# ADXL345_Breakout_V15panelize.net
KiCad netlist of a schematic drawn in EAGLE
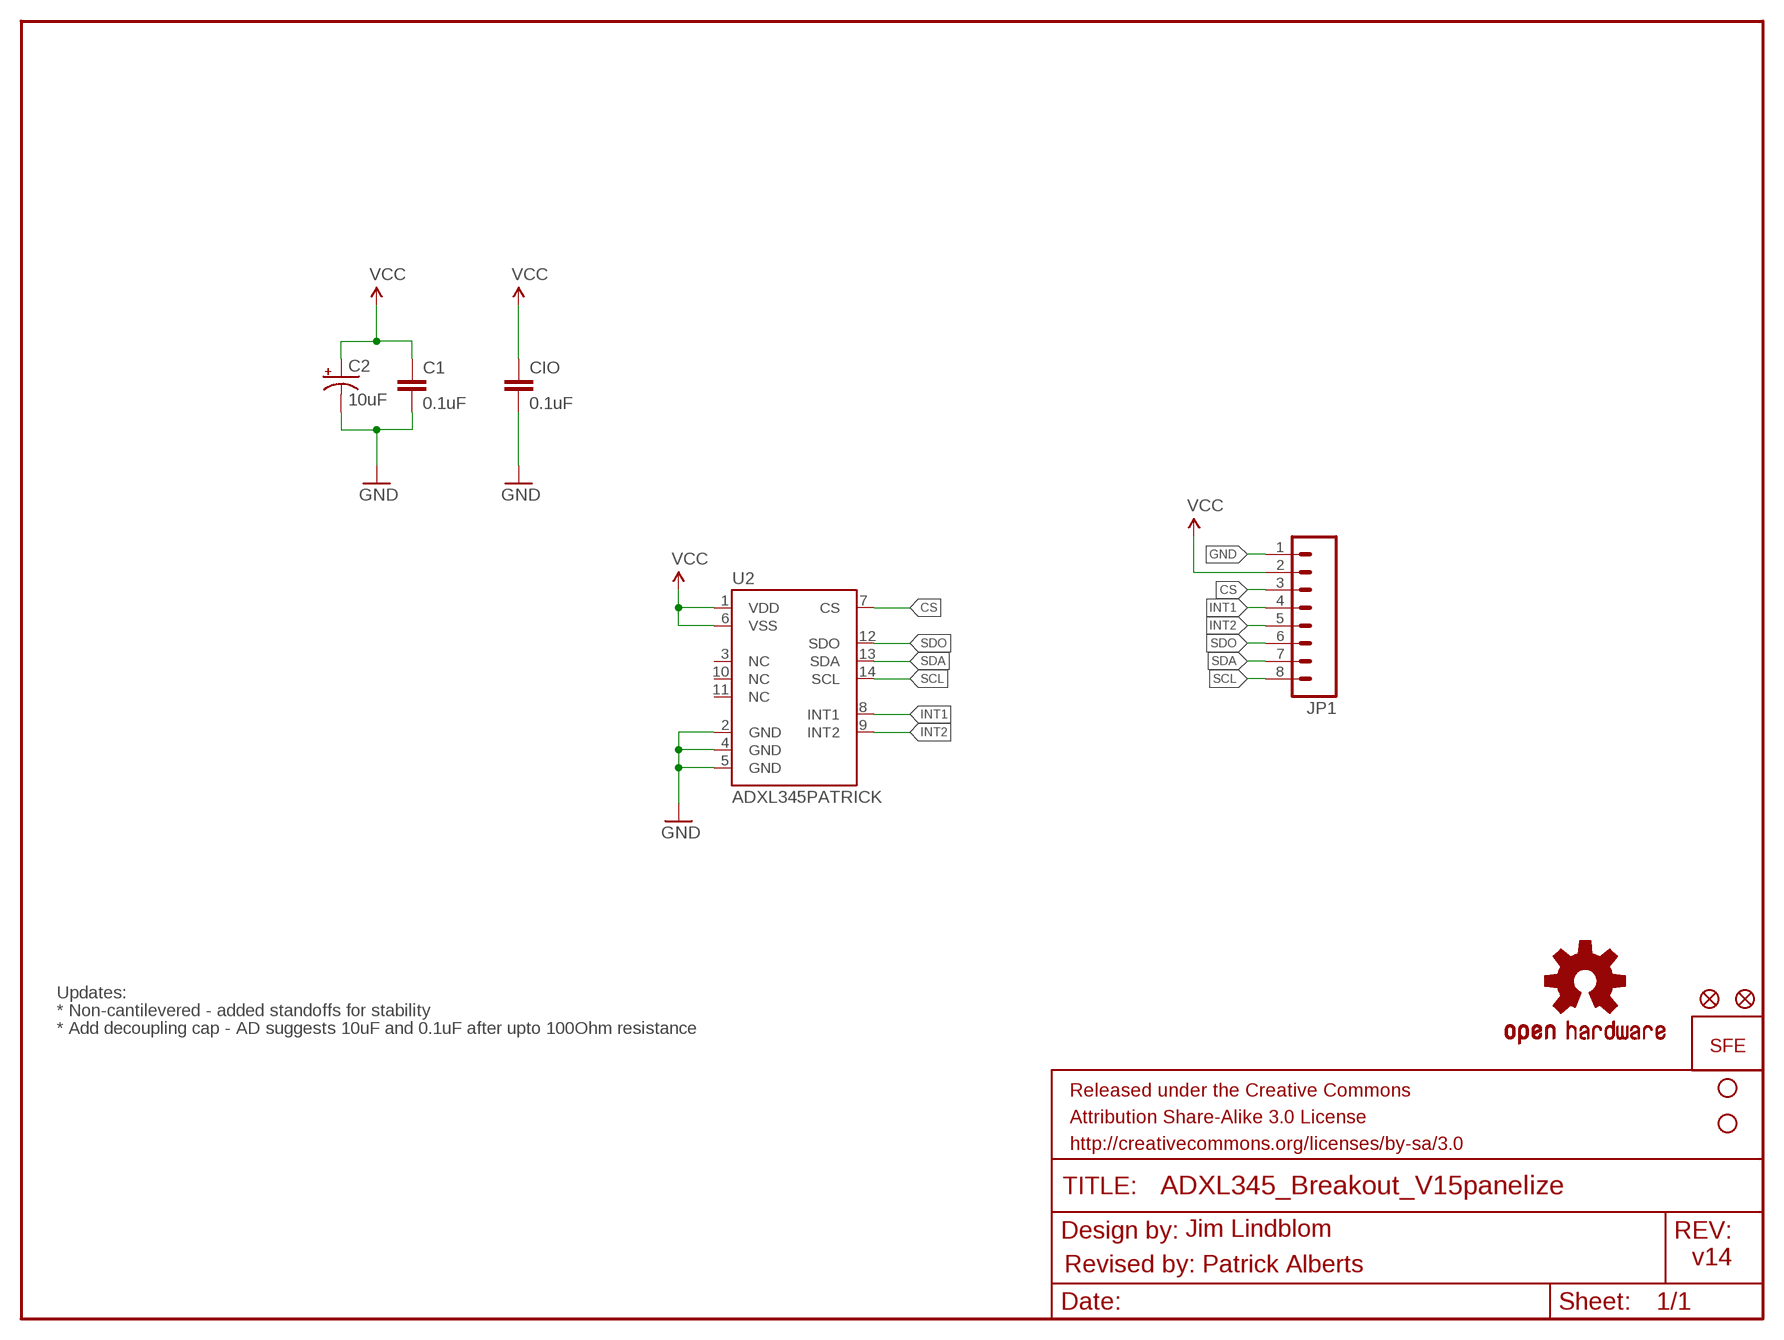
[diagram p0: schematic, sheet 1]

(export (version "E")
  (design (tool "Eeschema 10.0.6"))
  (components
    (comp (ref "C1")
      (value "0.1uF")
      (footprint "eagle-import:0805")
      (libsource (lib "eagle-import") (part "CAP0805"))
    )
    (comp (ref "C2")
      (value "10uF")
      (footprint "eagle-import:EIA3216")
      (libsource (lib "eagle-import") (part "CAP_POL1206"))
    )
    (comp (ref "CIO")
      (value "0.1uF")
      (footprint "eagle-import:0805")
      (libsource (lib "eagle-import") (part "CAP0805"))
    )
    (comp (ref "JP1")
      (value "M081X08")
      (footprint "eagle-import:1X08")
      (libsource (lib "eagle-import") (part "M081X08"))
    )
    (comp (ref "JP2")
      (value "STAND-OFF")
      (footprint "eagle-import:STAND-OFF")
      (libsource (lib "eagle-import") (part "STAND-OFF"))
    )
    (comp (ref "JP3")
      (value "STAND-OFF")
      (footprint "eagle-import:STAND-OFF")
      (libsource (lib "eagle-import") (part "STAND-OFF"))
    )
    (comp (ref "JP4")
      (value "FIDUCIAL1X2")
      (footprint "eagle-import:FIDUCIAL-1X2")
      (libsource (lib "eagle-import") (part "FIDUCIAL1X2"))
    )
    (comp (ref "JP5")
      (value "FIDUCIAL1X2")
      (footprint "eagle-import:FIDUCIAL-1X2")
      (libsource (lib "eagle-import") (part "FIDUCIAL1X2"))
    )
    (comp (ref "U$2")
      (value "LOGO-SFENEW")
      (footprint "eagle-import:SFE-NEW-WEBLOGO")
      (libsource (lib "eagle-import") (part "LOGO-SFENEW"))
    )
    (comp (ref "U$3")
      (value "OSHW-LOGOS")
      (footprint "eagle-import:OSHW-LOGO-S")
      (libsource (lib "eagle-import") (part "OSHW-LOGOS"))
    )
    (comp (ref "U2")
      (value "ADXL345PATRICK")
      (footprint "eagle-import:LGA14_1_1_PATRICK")
      (libsource (lib "eagle-import") (part "ADXL345PATRICK"))
    )
  )
  (nets
    (net (code "1") (name "CS") (class "Default")
      (node (ref "JP1") (pin "3") (pinfunction "3_3") (pintype "passive"))
      (node (ref "U2") (pin "7") (pinfunction "CS_7") (pintype "bidirectional"))
    )
    (net (code "2") (name "GND") (class "Default")
      (node (ref "C1") (pin "2") (pinfunction "2_2") (pintype "passive"))
      (node (ref "C2") (pin "C") (pinfunction "-_C") (pintype "passive"))
      (node (ref "CIO") (pin "2") (pinfunction "2_2") (pintype "passive"))
      (node (ref "JP1") (pin "1") (pinfunction "1_1") (pintype "passive"))
      (node (ref "U2") (pin "2") (pinfunction "GND_2") (pintype "bidirectional"))
      (node (ref "U2") (pin "4") (pinfunction "GND_4") (pintype "bidirectional"))
      (node (ref "U2") (pin "5") (pinfunction "GND_5") (pintype "bidirectional"))
    )
    (net (code "3") (name "INT1") (class "Default")
      (node (ref "JP1") (pin "4") (pinfunction "4_4") (pintype "passive"))
      (node (ref "U2") (pin "8") (pinfunction "INT1_8") (pintype "bidirectional"))
    )
    (net (code "4") (name "INT2") (class "Default")
      (node (ref "JP1") (pin "5") (pinfunction "5_5") (pintype "passive"))
      (node (ref "U2") (pin "9") (pinfunction "INT2_9") (pintype "bidirectional"))
    )
    (net (code "5") (name "SCL") (class "Default")
      (node (ref "JP1") (pin "8") (pinfunction "8_8") (pintype "passive"))
      (node (ref "U2") (pin "14") (pinfunction "SCL_14") (pintype "bidirectional"))
    )
    (net (code "6") (name "SDA") (class "Default")
      (node (ref "JP1") (pin "7") (pinfunction "7_7") (pintype "passive"))
      (node (ref "U2") (pin "13") (pinfunction "SDA_13") (pintype "bidirectional"))
    )
    (net (code "7") (name "SDO") (class "Default")
      (node (ref "JP1") (pin "6") (pinfunction "6_6") (pintype "passive"))
      (node (ref "U2") (pin "12") (pinfunction "SDO_12") (pintype "bidirectional"))
    )
    (net (code "8") (name "VCC") (class "Default")
      (node (ref "C1") (pin "1") (pinfunction "1_1") (pintype "passive"))
      (node (ref "C2") (pin "A") (pinfunction "+_A") (pintype "passive"))
      (node (ref "CIO") (pin "1") (pinfunction "1_1") (pintype "passive"))
      (node (ref "JP1") (pin "2") (pinfunction "2_2") (pintype "passive"))
      (node (ref "U2") (pin "1") (pinfunction "VDD_1") (pintype "bidirectional"))
      (node (ref "U2") (pin "6") (pinfunction "VSS_6") (pintype "bidirectional"))
    )
    (net (code "9") (name "unconnected-(U2-NC-Pad3)") (class "Default")
      (node (ref "U2") (pin "3") (pinfunction "NC_3") (pintype "bidirectional"))
    )
    (net (code "10") (name "unconnected-(U2-NC-Pad10)") (class "Default")
      (node (ref "U2") (pin "10") (pinfunction "NC_10") (pintype "bidirectional"))
    )
    (net (code "11") (name "unconnected-(U2-NC-Pad11)") (class "Default")
      (node (ref "U2") (pin "11") (pinfunction "NC_11") (pintype "bidirectional"))
    )
  )
)
